# battery-voltage-current-sensor.net
KiCad netlist of a schematic drawn in EAGLE
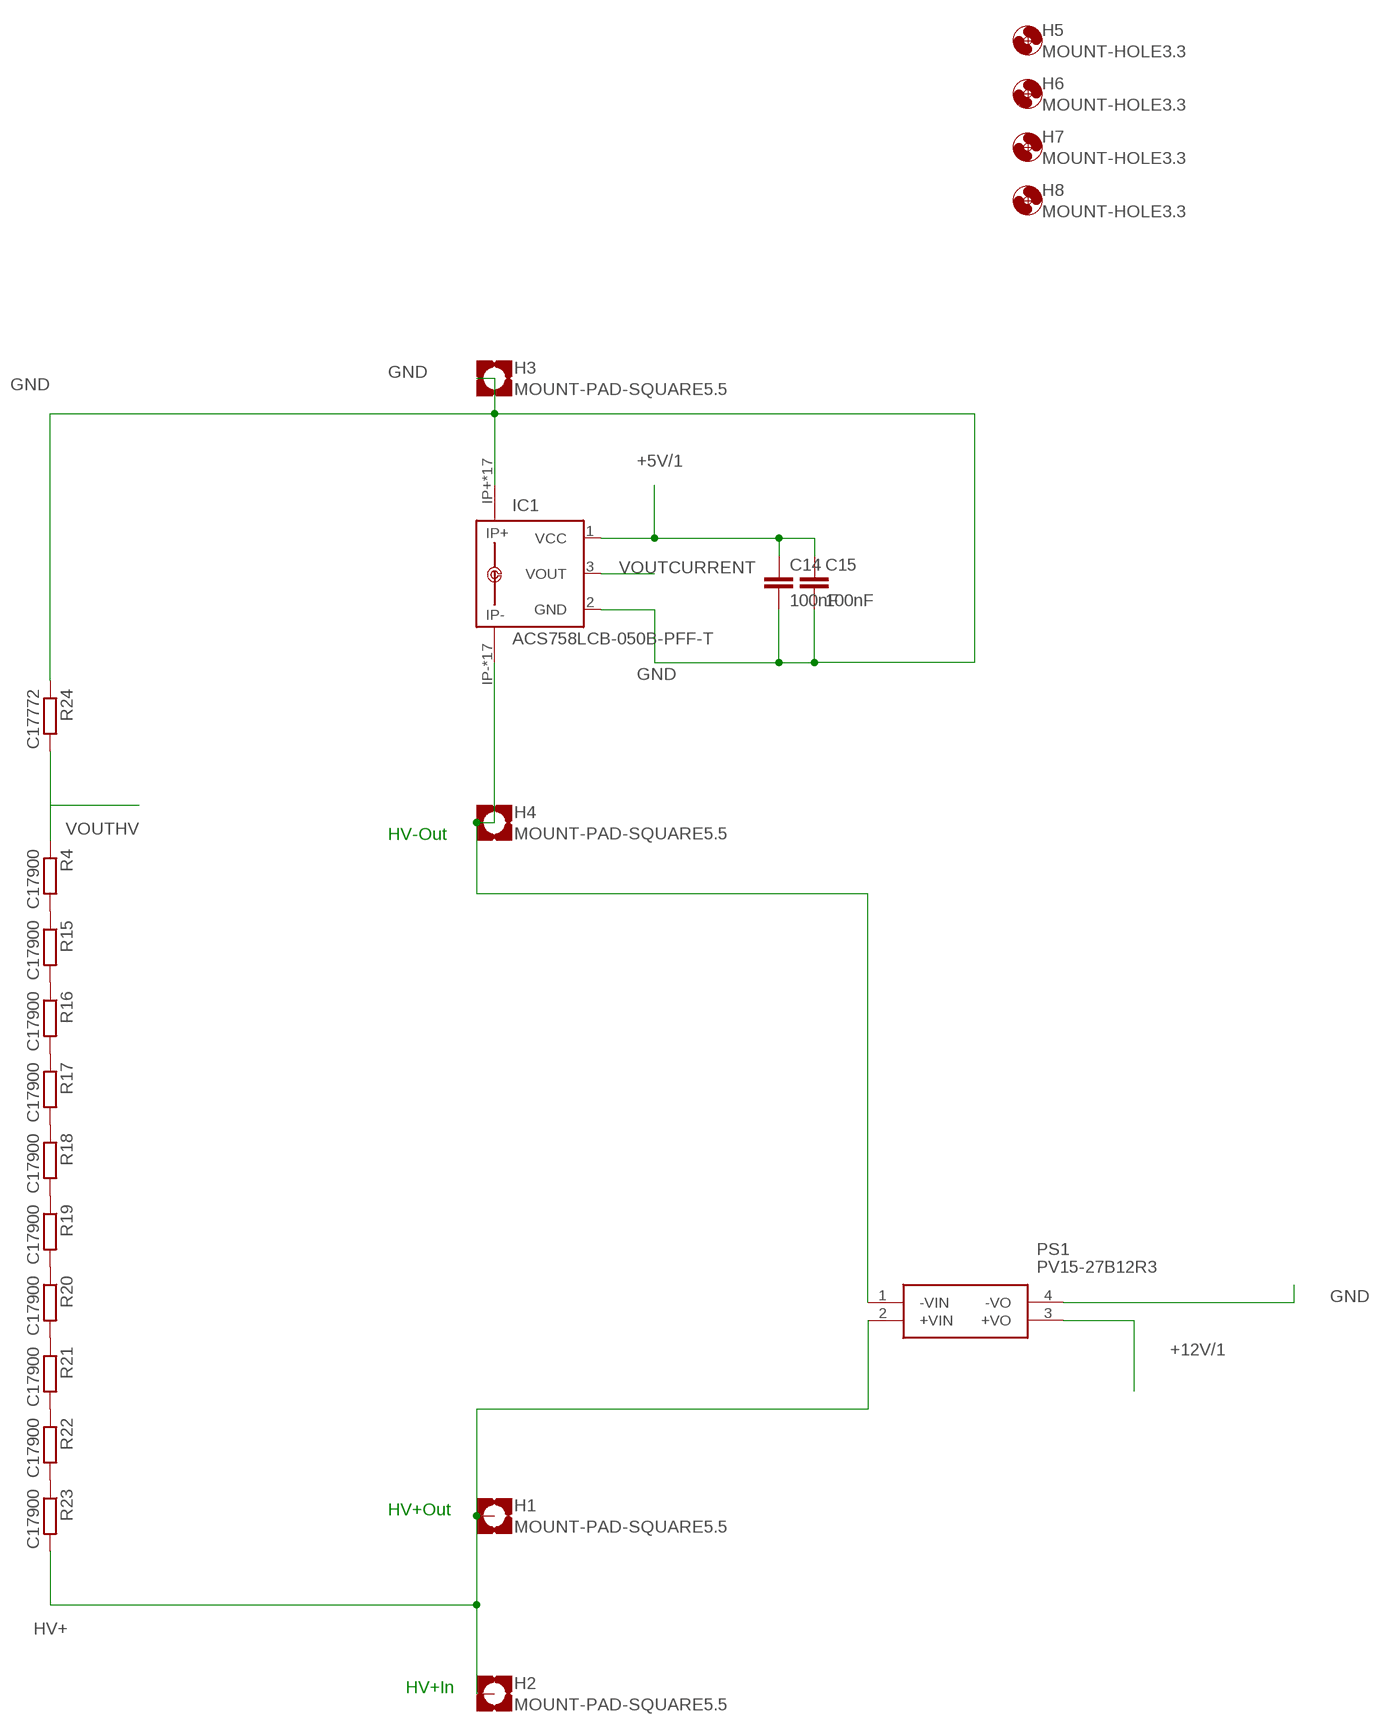
[diagram p0: schematic, sheet 1, part 1 of 2]
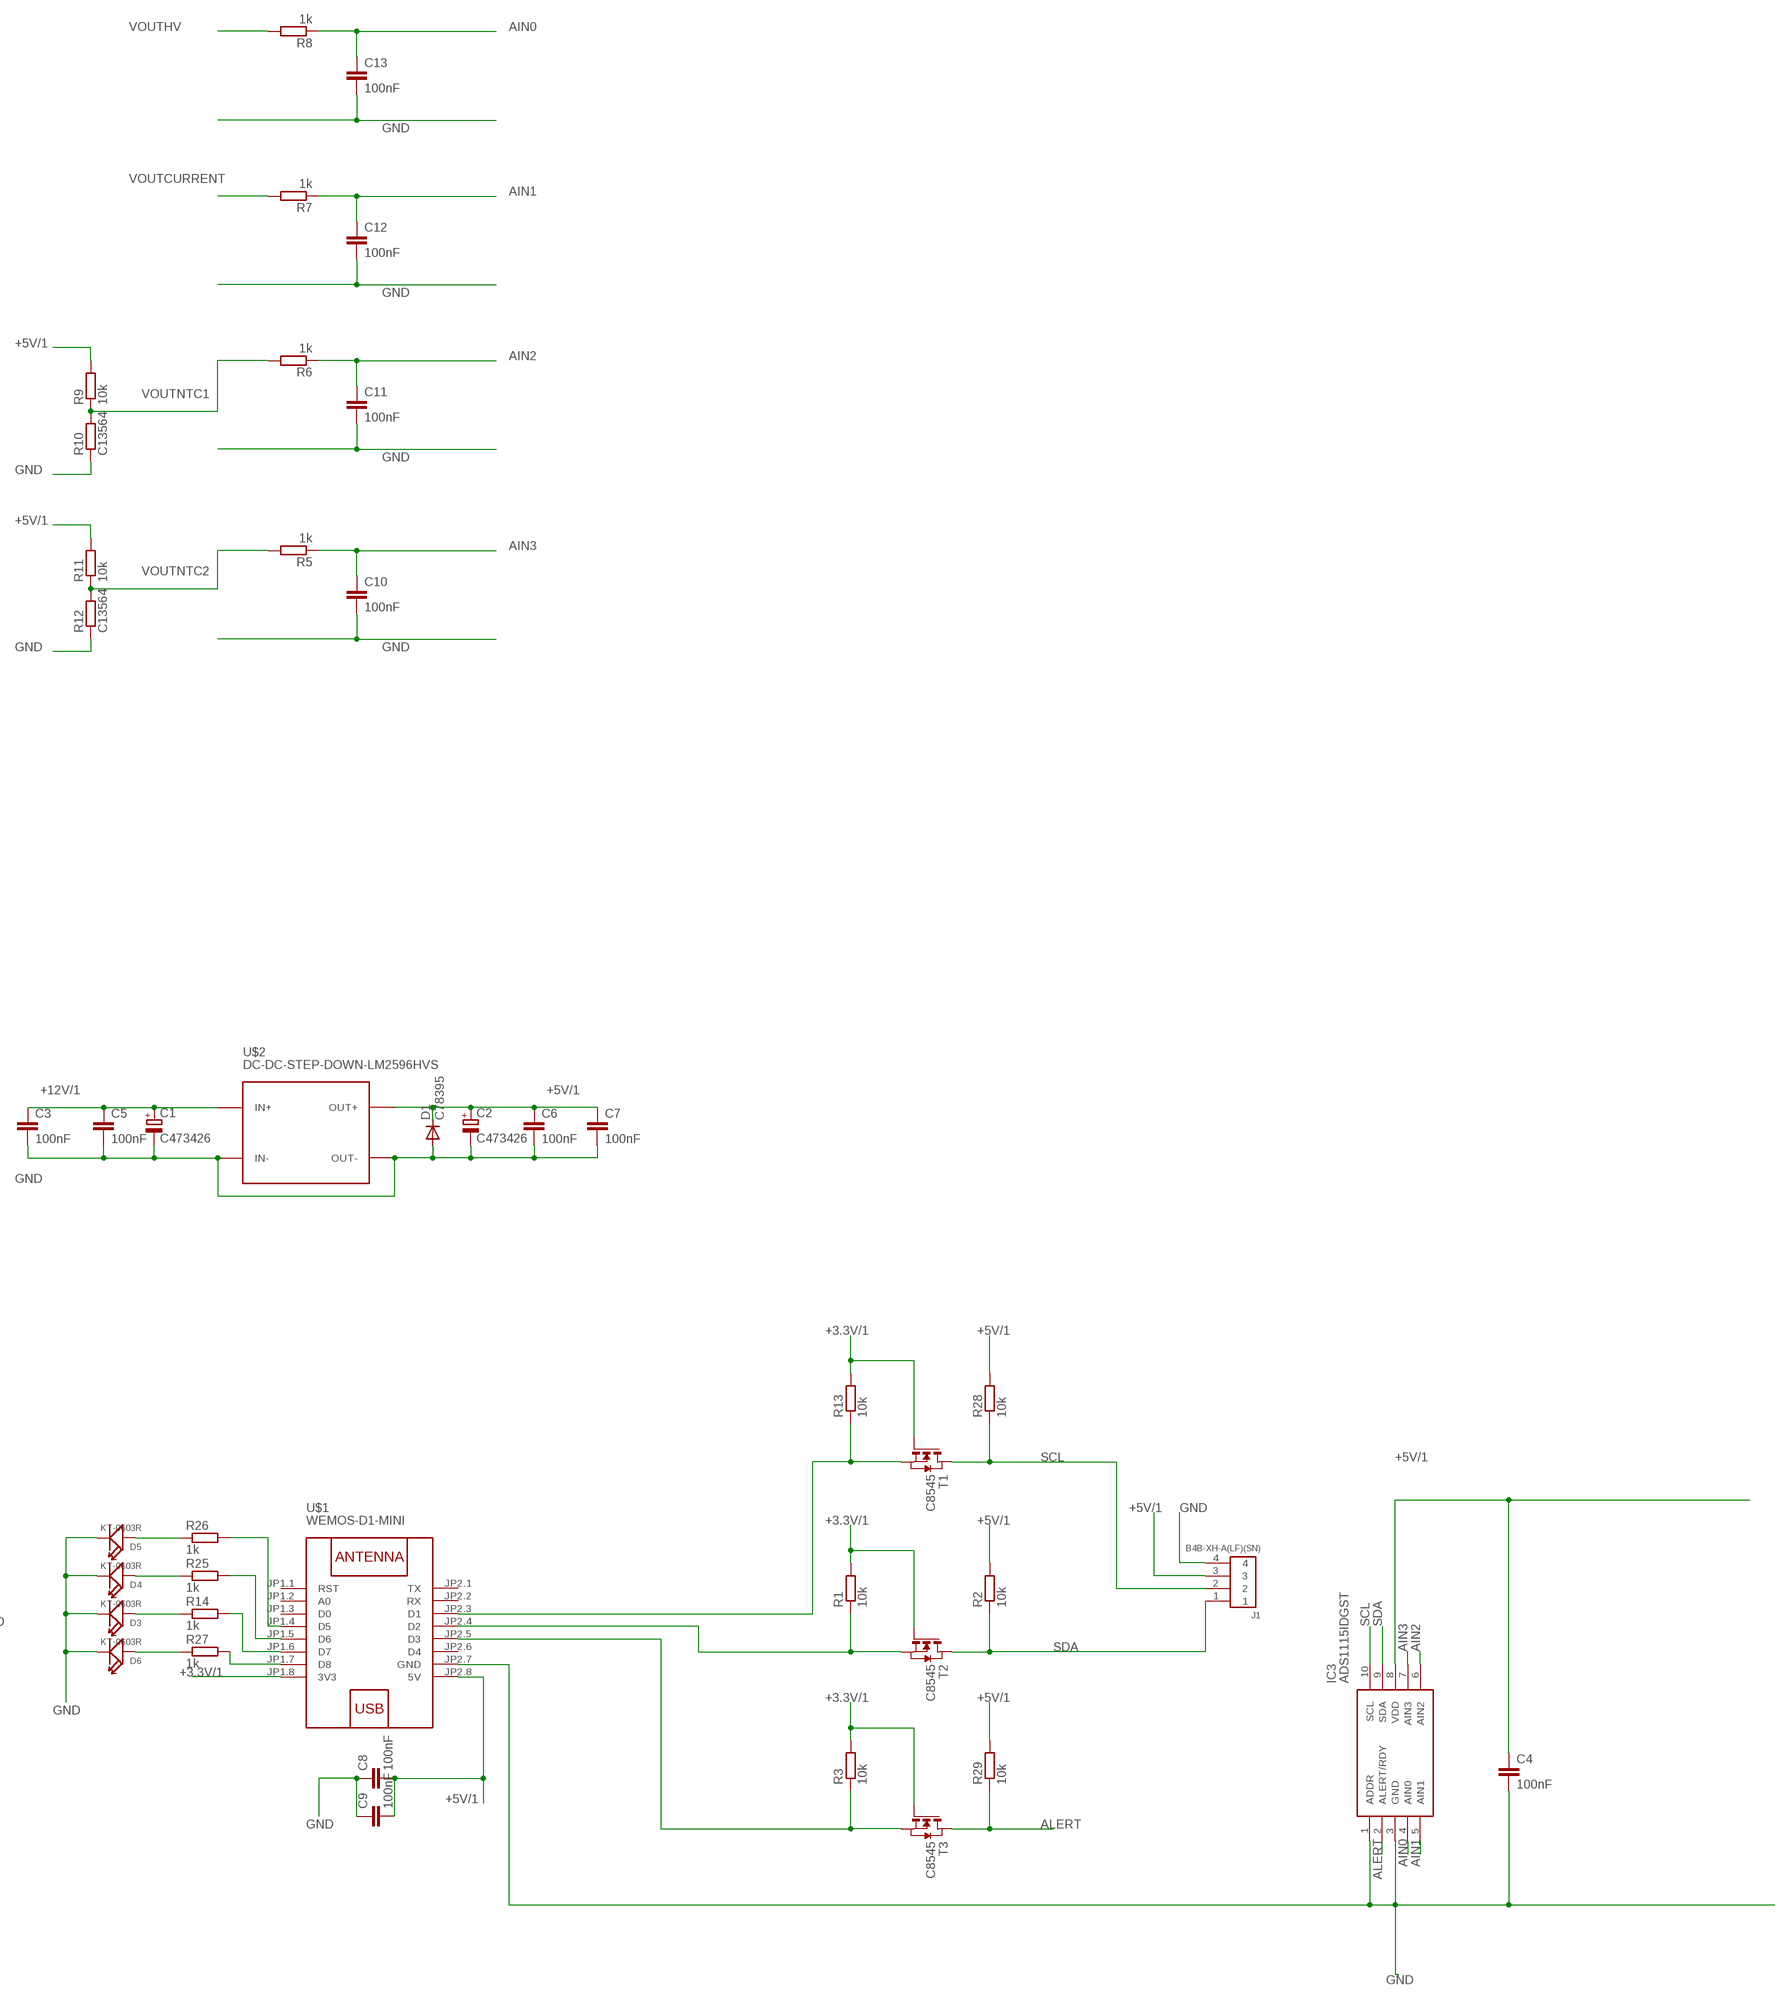
[diagram p1: schematic, sheet 1, part 2 of 2]

(export (version "E")
  (design (tool "Eeschema 10.0.6"))
  (components
    (comp (ref "C1")
      (value "C473426")
      (footprint "eagle-import:UD-6,3X7,7_NICHICON")
      (libsource (lib "eagle-import") (part "CPOL-EUUD-6,3X7,7"))
    )
    (comp (ref "C2")
      (value "C473426")
      (footprint "eagle-import:UD-6,3X7,7_NICHICON")
      (libsource (lib "eagle-import") (part "CPOL-EUUD-6,3X7,7"))
    )
    (comp (ref "C3")
      (value "100nF")
      (footprint "eagle-import:C0603")
      (libsource (lib "eagle-import") (part "C-EUC0603"))
    )
    (comp (ref "C4")
      (value "100nF")
      (footprint "eagle-import:C0805")
      (libsource (lib "eagle-import") (part "C-EUC0805"))
    )
    (comp (ref "C5")
      (value "100nF")
      (footprint "eagle-import:C0603")
      (libsource (lib "eagle-import") (part "C-EUC0603"))
    )
    (comp (ref "C6")
      (value "100nF")
      (footprint "eagle-import:C0603")
      (libsource (lib "eagle-import") (part "C-EUC0603"))
    )
    (comp (ref "C7")
      (value "100nF")
      (footprint "eagle-import:C0603")
      (libsource (lib "eagle-import") (part "C-EUC0603"))
    )
    (comp (ref "C8")
      (value "100nF")
      (footprint "eagle-import:C0603")
      (libsource (lib "eagle-import") (part "C-EUC0603"))
    )
    (comp (ref "C9")
      (value "100nF")
      (footprint "eagle-import:C0603")
      (libsource (lib "eagle-import") (part "C-EUC0603"))
    )
    (comp (ref "C10")
      (value "100nF")
      (footprint "eagle-import:C0603")
      (libsource (lib "eagle-import") (part "C-EUC0603"))
    )
    (comp (ref "C11")
      (value "100nF")
      (footprint "eagle-import:C0603")
      (libsource (lib "eagle-import") (part "C-EUC0603"))
    )
    (comp (ref "C12")
      (value "100nF")
      (footprint "eagle-import:C0603")
      (libsource (lib "eagle-import") (part "C-EUC0603"))
    )
    (comp (ref "C13")
      (value "100nF")
      (footprint "eagle-import:C0603")
      (libsource (lib "eagle-import") (part "C-EUC0603"))
    )
    (comp (ref "C14")
      (value "100nF")
      (footprint "eagle-import:C0603")
      (libsource (lib "eagle-import") (part "C-EUC0603"))
    )
    (comp (ref "C15")
      (value "100nF")
      (footprint "eagle-import:C0603")
      (libsource (lib "eagle-import") (part "C-EUC0603"))
    )
    (comp (ref "D1")
      (value "C78395")
      (footprint "eagle-import:SMB")
      (libsource (lib "eagle-import") (part "DIODE-SMB"))
    )
    (comp (ref "D3")
      (value "KT-0603R")
      (footprint "eagle-import:LED-0603")
      (fields (field (name "MF") "Everlight") (field (name "MP") "19-217/BHC-ZL1M2RY/3T"))
      (libsource (lib "eagle-import") (part "SMD-LED-CLEAR-BLUE(0603)"))
    )
    (comp (ref "D4")
      (value "KT-0603R")
      (footprint "eagle-import:LED-0603")
      (fields (field (name "MF") "Everlight") (field (name "MP") "19-217/BHC-ZL1M2RY/3T"))
      (libsource (lib "eagle-import") (part "SMD-LED-CLEAR-BLUE(0603)"))
    )
    (comp (ref "D5")
      (value "KT-0603R")
      (footprint "eagle-import:LED-0603")
      (fields (field (name "MF") "Everlight") (field (name "MP") "19-217/BHC-ZL1M2RY/3T"))
      (libsource (lib "eagle-import") (part "SMD-LED-CLEAR-BLUE(0603)"))
    )
    (comp (ref "D6")
      (value "KT-0603R")
      (footprint "eagle-import:LED-0603")
      (fields (field (name "MF") "Everlight") (field (name "MP") "19-217/BHC-ZL1M2RY/3T"))
      (libsource (lib "eagle-import") (part "SMD-LED-CLEAR-BLUE(0603)"))
    )
    (comp (ref "H1")
      (value "MOUNT-PAD-SQUARE5.5")
      (footprint "eagle-import:5,5-PAD-SQUARE")
      (libsource (lib "eagle-import") (part "MOUNT-PAD-SQUARE5.5"))
    )
    (comp (ref "H2")
      (value "MOUNT-PAD-SQUARE5.5")
      (footprint "eagle-import:5,5-PAD-SQUARE")
      (libsource (lib "eagle-import") (part "MOUNT-PAD-SQUARE5.5"))
    )
    (comp (ref "H3")
      (value "MOUNT-PAD-SQUARE5.5")
      (footprint "eagle-import:5,5-PAD-SQUARE")
      (libsource (lib "eagle-import") (part "MOUNT-PAD-SQUARE5.5"))
    )
    (comp (ref "H4")
      (value "MOUNT-PAD-SQUARE5.5")
      (footprint "eagle-import:5,5-PAD-SQUARE")
      (libsource (lib "eagle-import") (part "MOUNT-PAD-SQUARE5.5"))
    )
    (comp (ref "H5")
      (value "MOUNT-HOLE3.3")
      (footprint "eagle-import:3,3")
      (libsource (lib "eagle-import") (part "MOUNT-HOLE3.3"))
    )
    (comp (ref "H6")
      (value "MOUNT-HOLE3.3")
      (footprint "eagle-import:3,3")
      (libsource (lib "eagle-import") (part "MOUNT-HOLE3.3"))
    )
    (comp (ref "H7")
      (value "MOUNT-HOLE3.3")
      (footprint "eagle-import:3,3")
      (libsource (lib "eagle-import") (part "MOUNT-HOLE3.3"))
    )
    (comp (ref "H8")
      (value "MOUNT-HOLE3.3")
      (footprint "eagle-import:3,3")
      (libsource (lib "eagle-import") (part "MOUNT-HOLE3.3"))
    )
    (comp (ref "IC1")
      (value "ACS758LCB-050B-PFF-T")
      (footprint "eagle-import:CB-PFF")
      (libsource (lib "eagle-import") (part "ACS758LCB-050B-PFF-T"))
    )
    (comp (ref "IC3")
      (value "ADS1115IDGST")
      (footprint "eagle-import:SOP50P490X110-10N")
      (fields (field (name "MOUSER_PART_NUMBER") "595-ADS1115IDGST"))
      (libsource (lib "eagle-import") (part "ADS1115IDGST"))
    )
    (comp (ref "J1")
      (value "B4B-XH-A(LF)(SN)")
      (footprint "eagle-import:B4B-XH-A(LF)(SN)")
      (fields
        (field (name "DIGIKEY_PARTNO") "455-2249-ND")
        (field (name "MANUFACTURER") "JST Sales America Inc.")
        (field (name "CREATED_BY") "PCBLayout.com")
      )
      (libsource (lib "eagle-import") (part "B4B-XH-A(LF)(SN)"))
    )
    (comp (ref "PS1")
      (value "PV15-27B12R3")
      (footprint "eagle-import:PV1527B12R3")
      (libsource (lib "eagle-import") (part "PV15-27B12R3"))
    )
    (comp (ref "R1")
      (value "10k")
      (footprint "eagle-import:R0603")
      (libsource (lib "eagle-import") (part "R-EU_R0603"))
    )
    (comp (ref "R2")
      (value "10k")
      (footprint "eagle-import:R0603")
      (libsource (lib "eagle-import") (part "R-EU_R0603"))
    )
    (comp (ref "R3")
      (value "10k")
      (footprint "eagle-import:R0603")
      (libsource (lib "eagle-import") (part "R-EU_R0603"))
    )
    (comp (ref "R4")
      (value "C17900")
      (footprint "eagle-import:R1206")
      (libsource (lib "eagle-import") (part "R-EU_R1206"))
    )
    (comp (ref "R5")
      (value "1k")
      (footprint "eagle-import:R0805")
      (libsource (lib "eagle-import") (part "R-EU_R0805"))
    )
    (comp (ref "R6")
      (value "1k")
      (footprint "eagle-import:R0805")
      (libsource (lib "eagle-import") (part "R-EU_R0805"))
    )
    (comp (ref "R7")
      (value "1k")
      (footprint "eagle-import:R0805")
      (libsource (lib "eagle-import") (part "R-EU_R0805"))
    )
    (comp (ref "R8")
      (value "1k")
      (footprint "eagle-import:R0805")
      (libsource (lib "eagle-import") (part "R-EU_R0805"))
    )
    (comp (ref "R9")
      (value "10k")
      (footprint "eagle-import:R0603")
      (libsource (lib "eagle-import") (part "R-EU_R0603"))
    )
    (comp (ref "R10")
      (value "C13564")
      (footprint "eagle-import:R0603")
      (libsource (lib "eagle-import") (part "R-EU_R0603"))
    )
    (comp (ref "R11")
      (value "10k")
      (footprint "eagle-import:R0603")
      (libsource (lib "eagle-import") (part "R-EU_R0603"))
    )
    (comp (ref "R12")
      (value "C13564")
      (footprint "eagle-import:R0603")
      (libsource (lib "eagle-import") (part "R-EU_R0603"))
    )
    (comp (ref "R13")
      (value "10k")
      (footprint "eagle-import:R0603")
      (libsource (lib "eagle-import") (part "R-EU_R0603"))
    )
    (comp (ref "R14")
      (value "1k")
      (footprint "eagle-import:R0805")
      (libsource (lib "eagle-import") (part "R-EU_R0805"))
    )
    (comp (ref "R15")
      (value "C17900")
      (footprint "eagle-import:R1206")
      (libsource (lib "eagle-import") (part "R-EU_R1206"))
    )
    (comp (ref "R16")
      (value "C17900")
      (footprint "eagle-import:R1206")
      (libsource (lib "eagle-import") (part "R-EU_R1206"))
    )
    (comp (ref "R17")
      (value "C17900")
      (footprint "eagle-import:R1206")
      (libsource (lib "eagle-import") (part "R-EU_R1206"))
    )
    (comp (ref "R18")
      (value "C17900")
      (footprint "eagle-import:R1206")
      (libsource (lib "eagle-import") (part "R-EU_R1206"))
    )
    (comp (ref "R19")
      (value "C17900")
      (footprint "eagle-import:R1206")
      (libsource (lib "eagle-import") (part "R-EU_R1206"))
    )
    (comp (ref "R20")
      (value "C17900")
      (footprint "eagle-import:R1206")
      (libsource (lib "eagle-import") (part "R-EU_R1206"))
    )
    (comp (ref "R21")
      (value "C17900")
      (footprint "eagle-import:R1206")
      (libsource (lib "eagle-import") (part "R-EU_R1206"))
    )
    (comp (ref "R22")
      (value "C17900")
      (footprint "eagle-import:R1206")
      (libsource (lib "eagle-import") (part "R-EU_R1206"))
    )
    (comp (ref "R23")
      (value "C17900")
      (footprint "eagle-import:R1206")
      (libsource (lib "eagle-import") (part "R-EU_R1206"))
    )
    (comp (ref "R24")
      (value "C17772")
      (footprint "eagle-import:R0805")
      (libsource (lib "eagle-import") (part "R-EU_R0805"))
    )
    (comp (ref "R25")
      (value "1k")
      (footprint "eagle-import:R0805")
      (libsource (lib "eagle-import") (part "R-EU_R0805"))
    )
    (comp (ref "R26")
      (value "1k")
      (footprint "eagle-import:R0805")
      (libsource (lib "eagle-import") (part "R-EU_R0805"))
    )
    (comp (ref "R27")
      (value "1k")
      (footprint "eagle-import:R0805")
      (libsource (lib "eagle-import") (part "R-EU_R0805"))
    )
    (comp (ref "R28")
      (value "10k")
      (footprint "eagle-import:R0603")
      (libsource (lib "eagle-import") (part "R-EU_R0603"))
    )
    (comp (ref "R29")
      (value "10k")
      (footprint "eagle-import:R0603")
      (libsource (lib "eagle-import") (part "R-EU_R0603"))
    )
    (comp (ref "T1")
      (value "C8545")
      (footprint "eagle-import:SOT-23")
      (libsource (lib "eagle-import") (part "NMOSSOT23"))
    )
    (comp (ref "T2")
      (value "C8545")
      (footprint "eagle-import:SOT-23")
      (libsource (lib "eagle-import") (part "NMOSSOT23"))
    )
    (comp (ref "T3")
      (value "C8545")
      (footprint "eagle-import:SOT-23")
      (libsource (lib "eagle-import") (part "NMOSSOT23"))
    )
    (comp (ref "U$1")
      (value "WEMOS-D1-MINI")
      (footprint "eagle-import:WEMOS-D1-MINI")
      (libsource (lib "eagle-import") (part "WEMOS-D1-MINI"))
    )
    (comp (ref "U$2")
      (value "DC-DC-STEP-DOWN-LM2596HVS")
      (footprint "eagle-import:DC-DC-STEP-DOWN-LM2596HVS")
      (libsource (lib "eagle-import") (part "DC-DC-STEP-DOWN-LM2596HVS"))
    )
  )
  (nets
    (net (code "1") (name "/+3.3V{slash}1") (class "Default")
      (node (ref "R1") (pin "2") (pinfunction "2_2") (pintype "passive"))
      (node (ref "R13") (pin "2") (pinfunction "2_2") (pintype "passive"))
      (node (ref "R3") (pin "2") (pinfunction "2_2") (pintype "passive"))
      (node (ref "T1") (pin "3") (pinfunction "G_3") (pintype "passive"))
      (node (ref "T2") (pin "3") (pinfunction "G_3") (pintype "passive"))
      (node (ref "T3") (pin "3") (pinfunction "G_3") (pintype "passive"))
      (node (ref "U$1") (pin "JP1.8") (pinfunction "3V3_JP1.8") (pintype "power_in"))
    )
    (net (code "2") (name "/+5V{slash}1") (class "Default")
      (node (ref "C14") (pin "1") (pinfunction "1_1") (pintype "passive"))
      (node (ref "C15") (pin "1") (pinfunction "1_1") (pintype "passive"))
      (node (ref "C2") (pin "+") (pinfunction "+_+") (pintype "passive"))
      (node (ref "C4") (pin "1") (pinfunction "1_1") (pintype "passive"))
      (node (ref "C6") (pin "1") (pinfunction "1_1") (pintype "passive"))
      (node (ref "C7") (pin "1") (pinfunction "1_1") (pintype "passive"))
      (node (ref "C8") (pin "2") (pinfunction "2_2") (pintype "passive"))
      (node (ref "C9") (pin "2") (pinfunction "2_2") (pintype "passive"))
      (node (ref "D1") (pin "C") (pinfunction "C_C") (pintype "passive"))
      (node (ref "IC1") (pin "1") (pinfunction "VCC_1") (pintype "power_in"))
      (node (ref "IC3") (pin "8") (pinfunction "VDD_8") (pintype "bidirectional"))
      (node (ref "J1") (pin "3") (pinfunction "3_3") (pintype "passive"))
      (node (ref "R11") (pin "2") (pinfunction "2_2") (pintype "passive"))
      (node (ref "R2") (pin "2") (pinfunction "2_2") (pintype "passive"))
      (node (ref "R28") (pin "2") (pinfunction "2_2") (pintype "passive"))
      (node (ref "R29") (pin "2") (pinfunction "2_2") (pintype "passive"))
      (node (ref "R9") (pin "2") (pinfunction "2_2") (pintype "passive"))
      (node (ref "U$1") (pin "JP2.8") (pinfunction "5V_JP2.8") (pintype "power_in"))
      (node (ref "U$2") (pin "OUT+") (pinfunction "OUT+_OUT+") (pintype "bidirectional"))
    )
    (net (code "3") (name "/+12V{slash}1") (class "Default")
      (node (ref "C1") (pin "+") (pinfunction "+_+") (pintype "passive"))
      (node (ref "C3") (pin "1") (pinfunction "1_1") (pintype "passive"))
      (node (ref "C5") (pin "1") (pinfunction "1_1") (pintype "passive"))
      (node (ref "PS1") (pin "3") (pinfunction "+VO_3") (pintype "bidirectional"))
      (node (ref "U$2") (pin "IN+") (pinfunction "IN+_IN+") (pintype "bidirectional"))
    )
    (net (code "4") (name "/AIN0") (class "Default")
      (node (ref "C13") (pin "1") (pinfunction "1_1") (pintype "passive"))
      (node (ref "IC3") (pin "4") (pinfunction "AIN0_4") (pintype "bidirectional"))
      (node (ref "R8") (pin "1") (pinfunction "1_1") (pintype "passive"))
    )
    (net (code "5") (name "/AIN1") (class "Default")
      (node (ref "C12") (pin "1") (pinfunction "1_1") (pintype "passive"))
      (node (ref "IC3") (pin "5") (pinfunction "AIN1_5") (pintype "bidirectional"))
      (node (ref "R7") (pin "1") (pinfunction "1_1") (pintype "passive"))
    )
    (net (code "6") (name "/AIN2") (class "Default")
      (node (ref "C11") (pin "1") (pinfunction "1_1") (pintype "passive"))
      (node (ref "IC3") (pin "6") (pinfunction "AIN2_6") (pintype "bidirectional"))
      (node (ref "R6") (pin "1") (pinfunction "1_1") (pintype "passive"))
    )
    (net (code "7") (name "/AIN3") (class "Default")
      (node (ref "C10") (pin "1") (pinfunction "1_1") (pintype "passive"))
      (node (ref "IC3") (pin "7") (pinfunction "AIN3_7") (pintype "bidirectional"))
      (node (ref "R5") (pin "1") (pinfunction "1_1") (pintype "passive"))
    )
    (net (code "8") (name "/ALERT") (class "Default")
      (node (ref "IC3") (pin "2") (pinfunction "ALERT/RDY_2") (pintype "bidirectional"))
      (node (ref "R29") (pin "1") (pinfunction "1_1") (pintype "passive"))
      (node (ref "T3") (pin "1") (pinfunction "D_1") (pintype "passive"))
    )
    (net (code "9") (name "/GND") (class "Default")
      (node (ref "C1") (pin "-") (pinfunction "-_-") (pintype "passive"))
      (node (ref "C10") (pin "2") (pinfunction "2_2") (pintype "passive"))
      (node (ref "C11") (pin "2") (pinfunction "2_2") (pintype "passive"))
      (node (ref "C12") (pin "2") (pinfunction "2_2") (pintype "passive"))
      (node (ref "C13") (pin "2") (pinfunction "2_2") (pintype "passive"))
      (node (ref "C14") (pin "2") (pinfunction "2_2") (pintype "passive"))
      (node (ref "C15") (pin "2") (pinfunction "2_2") (pintype "passive"))
      (node (ref "C2") (pin "-") (pinfunction "-_-") (pintype "passive"))
      (node (ref "C3") (pin "2") (pinfunction "2_2") (pintype "passive"))
      (node (ref "C4") (pin "2") (pinfunction "2_2") (pintype "passive"))
      (node (ref "C5") (pin "2") (pinfunction "2_2") (pintype "passive"))
      (node (ref "C6") (pin "2") (pinfunction "2_2") (pintype "passive"))
      (node (ref "C7") (pin "2") (pinfunction "2_2") (pintype "passive"))
      (node (ref "C8") (pin "1") (pinfunction "1_1") (pintype "passive"))
      (node (ref "C9") (pin "1") (pinfunction "1_1") (pintype "passive"))
      (node (ref "D1") (pin "A") (pinfunction "A_A") (pintype "passive"))
      (node (ref "D3") (pin "-") (pinfunction "-_-") (pintype "passive"))
      (node (ref "D4") (pin "-") (pinfunction "-_-") (pintype "passive"))
      (node (ref "D5") (pin "-") (pinfunction "-_-") (pintype "passive"))
      (node (ref "D6") (pin "-") (pinfunction "-_-") (pintype "passive"))
      (node (ref "H3") (pin "B5,5") (pinfunction "MOUNT_B5,5") (pintype "passive"))
      (node (ref "IC1") (pin "2") (pinfunction "GND_2") (pintype "power_in"))
      (node (ref "IC1") (pin "IP+") (pinfunction "IP+_IP+") (pintype "passive"))
      (node (ref "IC1") (pin "IP+@10") (pinfunction "IP+_IP+@10") (pintype "passive"))
      (node (ref "IC1") (pin "IP+@11") (pinfunction "IP+_IP+@11") (pintype "passive"))
      (node (ref "IC1") (pin "IP+@12") (pinfunction "IP+_IP+@12") (pintype "passive"))
      (node (ref "IC1") (pin "IP+@13") (pinfunction "IP+_IP+@13") (pintype "passive"))
      (node (ref "IC1") (pin "IP+@14") (pinfunction "IP+_IP+@14") (pintype "passive"))
      (node (ref "IC1") (pin "IP+@15") (pinfunction "IP+_IP+@15") (pintype "passive"))
      (node (ref "IC1") (pin "IP+@16") (pinfunction "IP+_IP+@16") (pintype "passive"))
      (node (ref "IC1") (pin "IP+@17") (pinfunction "IP+_IP+@17") (pintype "passive"))
      (node (ref "IC1") (pin "IP+@2") (pinfunction "IP+_IP+@2") (pintype "passive"))
      (node (ref "IC1") (pin "IP+@3") (pinfunction "IP+_IP+@3") (pintype "passive"))
      (node (ref "IC1") (pin "IP+@4") (pinfunction "IP+_IP+@4") (pintype "passive"))
      (node (ref "IC1") (pin "IP+@5") (pinfunction "IP+_IP+@5") (pintype "passive"))
      (node (ref "IC1") (pin "IP+@6") (pinfunction "IP+_IP+@6") (pintype "passive"))
      (node (ref "IC1") (pin "IP+@7") (pinfunction "IP+_IP+@7") (pintype "passive"))
      (node (ref "IC1") (pin "IP+@8") (pinfunction "IP+_IP+@8") (pintype "passive"))
      (node (ref "IC1") (pin "IP+@9") (pinfunction "IP+_IP+@9") (pintype "passive"))
      (node (ref "IC3") (pin "1") (pinfunction "ADDR_1") (pintype "bidirectional"))
      (node (ref "IC3") (pin "3") (pinfunction "GND_3") (pintype "bidirectional"))
      (node (ref "J1") (pin "4") (pinfunction "4_4") (pintype "passive"))
      (node (ref "PS1") (pin "4") (pinfunction "-VO_4") (pintype "bidirectional"))
      (node (ref "R10") (pin "1") (pinfunction "1_1") (pintype "passive"))
      (node (ref "R12") (pin "1") (pinfunction "1_1") (pintype "passive"))
      (node (ref "R24") (pin "1") (pinfunction "1_1") (pintype "passive"))
      (node (ref "U$1") (pin "JP2.7") (pinfunction "GND_JP2.7") (pintype "power_in"))
      (node (ref "U$2") (pin "IN-") (pinfunction "IN-_IN-") (pintype "bidirectional"))
      (node (ref "U$2") (pin "OUT-") (pinfunction "OUT-_OUT-") (pintype "bidirectional"))
    )
    (net (code "10") (name "/HV+") (class "Default")
      (node (ref "H1") (pin "B5,5") (pinfunction "MOUNT_B5,5") (pintype "passive"))
      (node (ref "H2") (pin "B5,5") (pinfunction "MOUNT_B5,5") (pintype "passive"))
      (node (ref "PS1") (pin "2") (pinfunction "+VIN_2") (pintype "bidirectional"))
      (node (ref "R23") (pin "2") (pinfunction "2_2") (pintype "passive"))
    )
    (net (code "11") (name "/SCL") (class "Default")
      (node (ref "IC3") (pin "10") (pinfunction "SCL_10") (pintype "bidirectional"))
      (node (ref "J1") (pin "2") (pinfunction "2_2") (pintype "passive"))
      (node (ref "R28") (pin "1") (pinfunction "1_1") (pintype "passive"))
      (node (ref "T1") (pin "1") (pinfunction "D_1") (pintype "passive"))
    )
    (net (code "12") (name "/SDA") (class "Default")
      (node (ref "IC3") (pin "9") (pinfunction "SDA_9") (pintype "bidirectional"))
      (node (ref "J1") (pin "1") (pinfunction "1_1") (pintype "passive"))
      (node (ref "R2") (pin "1") (pinfunction "1_1") (pintype "passive"))
      (node (ref "T2") (pin "1") (pinfunction "D_1") (pintype "passive"))
    )
    (net (code "13") (name "/VOUTCURRENT") (class "Default")
      (node (ref "IC1") (pin "3") (pinfunction "VOUT_3") (pintype "output"))
      (node (ref "R7") (pin "2") (pinfunction "2_2") (pintype "passive"))
    )
    (net (code "14") (name "/VOUTHV") (class "Default")
      (node (ref "R24") (pin "2") (pinfunction "2_2") (pintype "passive"))
      (node (ref "R4") (pin "1") (pinfunction "1_1") (pintype "passive"))
      (node (ref "R8") (pin "2") (pinfunction "2_2") (pintype "passive"))
    )
    (net (code "15") (name "/VOUTNTC1") (class "Default")
      (node (ref "R10") (pin "2") (pinfunction "2_2") (pintype "passive"))
      (node (ref "R6") (pin "2") (pinfunction "2_2") (pintype "passive"))
      (node (ref "R9") (pin "1") (pinfunction "1_1") (pintype "passive"))
    )
    (net (code "16") (name "/VOUTNTC2") (class "Default")
      (node (ref "R11") (pin "1") (pinfunction "1_1") (pintype "passive"))
      (node (ref "R12") (pin "2") (pinfunction "2_2") (pintype "passive"))
      (node (ref "R5") (pin "2") (pinfunction "2_2") (pintype "passive"))
    )
    (net (code "17") (name "Net-(D3-Pad+)") (class "Default")
      (node (ref "D3") (pin "+") (pinfunction "+_+") (pintype "passive"))
      (node (ref "R14") (pin "1") (pinfunction "1_1") (pintype "passive"))
    )
    (net (code "18") (name "Net-(D4-Pad+)") (class "Default")
      (node (ref "D4") (pin "+") (pinfunction "+_+") (pintype "passive"))
      (node (ref "R25") (pin "1") (pinfunction "1_1") (pintype "passive"))
    )
    (net (code "19") (name "Net-(D5-Pad+)") (class "Default")
      (node (ref "D5") (pin "+") (pinfunction "+_+") (pintype "passive"))
      (node (ref "R26") (pin "1") (pinfunction "1_1") (pintype "passive"))
    )
    (net (code "20") (name "Net-(D6-Pad+)") (class "Default")
      (node (ref "D6") (pin "+") (pinfunction "+_+") (pintype "passive"))
      (node (ref "R27") (pin "1") (pinfunction "1_1") (pintype "passive"))
    )
    (net (code "21") (name "Net-(H4-MOUNT)") (class "Default")
      (node (ref "H4") (pin "B5,5") (pinfunction "MOUNT_B5,5") (pintype "passive"))
      (node (ref "IC1") (pin "IP-") (pinfunction "IP-_IP-") (pintype "passive"))
      (node (ref "IC1") (pin "IP-@10") (pinfunction "IP-_IP-@10") (pintype "passive"))
      (node (ref "IC1") (pin "IP-@11") (pinfunction "IP-_IP-@11") (pintype "passive"))
      (node (ref "IC1") (pin "IP-@12") (pinfunction "IP-_IP-@12") (pintype "passive"))
      (node (ref "IC1") (pin "IP-@13") (pinfunction "IP-_IP-@13") (pintype "passive"))
      (node (ref "IC1") (pin "IP-@14") (pinfunction "IP-_IP-@14") (pintype "passive"))
      (node (ref "IC1") (pin "IP-@15") (pinfunction "IP-_IP-@15") (pintype "passive"))
      (node (ref "IC1") (pin "IP-@16") (pinfunction "IP-_IP-@16") (pintype "passive"))
      (node (ref "IC1") (pin "IP-@17") (pinfunction "IP-_IP-@17") (pintype "passive"))
      (node (ref "IC1") (pin "IP-@2") (pinfunction "IP-_IP-@2") (pintype "passive"))
      (node (ref "IC1") (pin "IP-@3") (pinfunction "IP-_IP-@3") (pintype "passive"))
      (node (ref "IC1") (pin "IP-@4") (pinfunction "IP-_IP-@4") (pintype "passive"))
      (node (ref "IC1") (pin "IP-@5") (pinfunction "IP-_IP-@5") (pintype "passive"))
      (node (ref "IC1") (pin "IP-@6") (pinfunction "IP-_IP-@6") (pintype "passive"))
      (node (ref "IC1") (pin "IP-@7") (pinfunction "IP-_IP-@7") (pintype "passive"))
      (node (ref "IC1") (pin "IP-@8") (pinfunction "IP-_IP-@8") (pintype "passive"))
      (node (ref "IC1") (pin "IP-@9") (pinfunction "IP-_IP-@9") (pintype "passive"))
      (node (ref "PS1") (pin "1") (pinfunction "-VIN_1") (pintype "bidirectional"))
    )
    (net (code "22") (name "Net-(R15-Pad1)") (class "Default")
      (node (ref "R15") (pin "1") (pinfunction "1_1") (pintype "passive"))
      (node (ref "R4") (pin "2") (pinfunction "2_2") (pintype "passive"))
    )
    (net (code "23") (name "Net-(R15-Pad2)") (class "Default")
      (node (ref "R15") (pin "2") (pinfunction "2_2") (pintype "passive"))
      (node (ref "R16") (pin "1") (pinfunction "1_1") (pintype "passive"))
    )
    (net (code "24") (name "Net-(R16-Pad2)") (class "Default")
      (node (ref "R16") (pin "2") (pinfunction "2_2") (pintype "passive"))
      (node (ref "R17") (pin "1") (pinfunction "1_1") (pintype "passive"))
    )
    (net (code "25") (name "Net-(R17-Pad2)") (class "Default")
      (node (ref "R17") (pin "2") (pinfunction "2_2") (pintype "passive"))
      (node (ref "R18") (pin "1") (pinfunction "1_1") (pintype "passive"))
    )
    (net (code "26") (name "Net-(R18-Pad2)") (class "Default")
      (node (ref "R18") (pin "2") (pinfunction "2_2") (pintype "passive"))
      (node (ref "R19") (pin "1") (pinfunction "1_1") (pintype "passive"))
    )
    (net (code "27") (name "Net-(R19-Pad2)") (class "Default")
      (node (ref "R19") (pin "2") (pinfunction "2_2") (pintype "passive"))
      (node (ref "R20") (pin "1") (pinfunction "1_1") (pintype "passive"))
    )
    (net (code "28") (name "Net-(R20-Pad2)") (class "Default")
      (node (ref "R20") (pin "2") (pinfunction "2_2") (pintype "passive"))
      (node (ref "R21") (pin "1") (pinfunction "1_1") (pintype "passive"))
    )
    (net (code "29") (name "Net-(R21-Pad2)") (class "Default")
      (node (ref "R21") (pin "2") (pinfunction "2_2") (pintype "passive"))
      (node (ref "R22") (pin "1") (pinfunction "1_1") (pintype "passive"))
    )
    (net (code "30") (name "Net-(R22-Pad2)") (class "Default")
      (node (ref "R22") (pin "2") (pinfunction "2_2") (pintype "passive"))
      (node (ref "R23") (pin "1") (pinfunction "1_1") (pintype "passive"))
    )
    (net (code "31") (name "Net-(T1-S)") (class "Default")
      (node (ref "R13") (pin "1") (pinfunction "1_1") (pintype "passive"))
      (node (ref "T1") (pin "2") (pinfunction "S_2") (pintype "passive"))
      (node (ref "U$1") (pin "JP2.3") (pinfunction "D1_JP2.3") (pintype "bidirectional"))
    )
    (net (code "32") (name "Net-(T2-S)") (class "Default")
      (node (ref "R1") (pin "1") (pinfunction "1_1") (pintype "passive"))
      (node (ref "T2") (pin "2") (pinfunction "S_2") (pintype "passive"))
      (node (ref "U$1") (pin "JP2.4") (pinfunction "D2_JP2.4") (pintype "bidirectional"))
    )
    (net (code "33") (name "Net-(T3-S)") (class "Default")
      (node (ref "R3") (pin "1") (pinfunction "1_1") (pintype "passive"))
      (node (ref "T3") (pin "2") (pinfunction "S_2") (pintype "passive"))
      (node (ref "U$1") (pin "JP2.5") (pinfunction "D3_JP2.5") (pintype "bidirectional"))
    )
    (net (code "34") (name "Net-(U$1-D5)") (class "Default")
      (node (ref "R26") (pin "2") (pinfunction "2_2") (pintype "passive"))
      (node (ref "U$1") (pin "JP1.4") (pinfunction "D5_JP1.4") (pintype "bidirectional"))
    )
    (net (code "35") (name "Net-(U$1-D6)") (class "Default")
      (node (ref "R25") (pin "2") (pinfunction "2_2") (pintype "passive"))
      (node (ref "U$1") (pin "JP1.5") (pinfunction "D6_JP1.5") (pintype "bidirectional"))
    )
    (net (code "36") (name "Net-(U$1-D7)") (class "Default")
      (node (ref "R14") (pin "2") (pinfunction "2_2") (pintype "passive"))
      (node (ref "U$1") (pin "JP1.6") (pinfunction "D7_JP1.6") (pintype "bidirectional"))
    )
    (net (code "37") (name "Net-(U$1-D8)") (class "Default")
      (node (ref "R27") (pin "2") (pinfunction "2_2") (pintype "passive"))
      (node (ref "U$1") (pin "JP1.7") (pinfunction "D8_JP1.7") (pintype "bidirectional"))
    )
    (net (code "38") (name "unconnected-(U$1-A0-PadJP1.2)") (class "Default")
      (node (ref "U$1") (pin "JP1.2") (pinfunction "A0_JP1.2") (pintype "bidirectional"))
    )
    (net (code "39") (name "unconnected-(U$1-D0-PadJP1.3)") (class "Default")
      (node (ref "U$1") (pin "JP1.3") (pinfunction "D0_JP1.3") (pintype "bidirectional"))
    )
    (net (code "40") (name "unconnected-(U$1-D4-PadJP2.6)") (class "Default")
      (node (ref "U$1") (pin "JP2.6") (pinfunction "D4_JP2.6") (pintype "bidirectional"))
    )
    (net (code "41") (name "unconnected-(U$1-RST-PadJP1.1)") (class "Default")
      (node (ref "U$1") (pin "JP1.1") (pinfunction "RST_JP1.1") (pintype "bidirectional"))
    )
    (net (code "42") (name "unconnected-(U$1-RX-PadJP2.2)") (class "Default")
      (node (ref "U$1") (pin "JP2.2") (pinfunction "RX_JP2.2") (pintype "bidirectional"))
    )
    (net (code "43") (name "unconnected-(U$1-TX-PadJP2.1)") (class "Default")
      (node (ref "U$1") (pin "JP2.1") (pinfunction "TX_JP2.1") (pintype "bidirectional"))
    )
  )
)
